# Power_SolenoidKill.net
KiCad netlist of a schematic drawn in Altium Designer
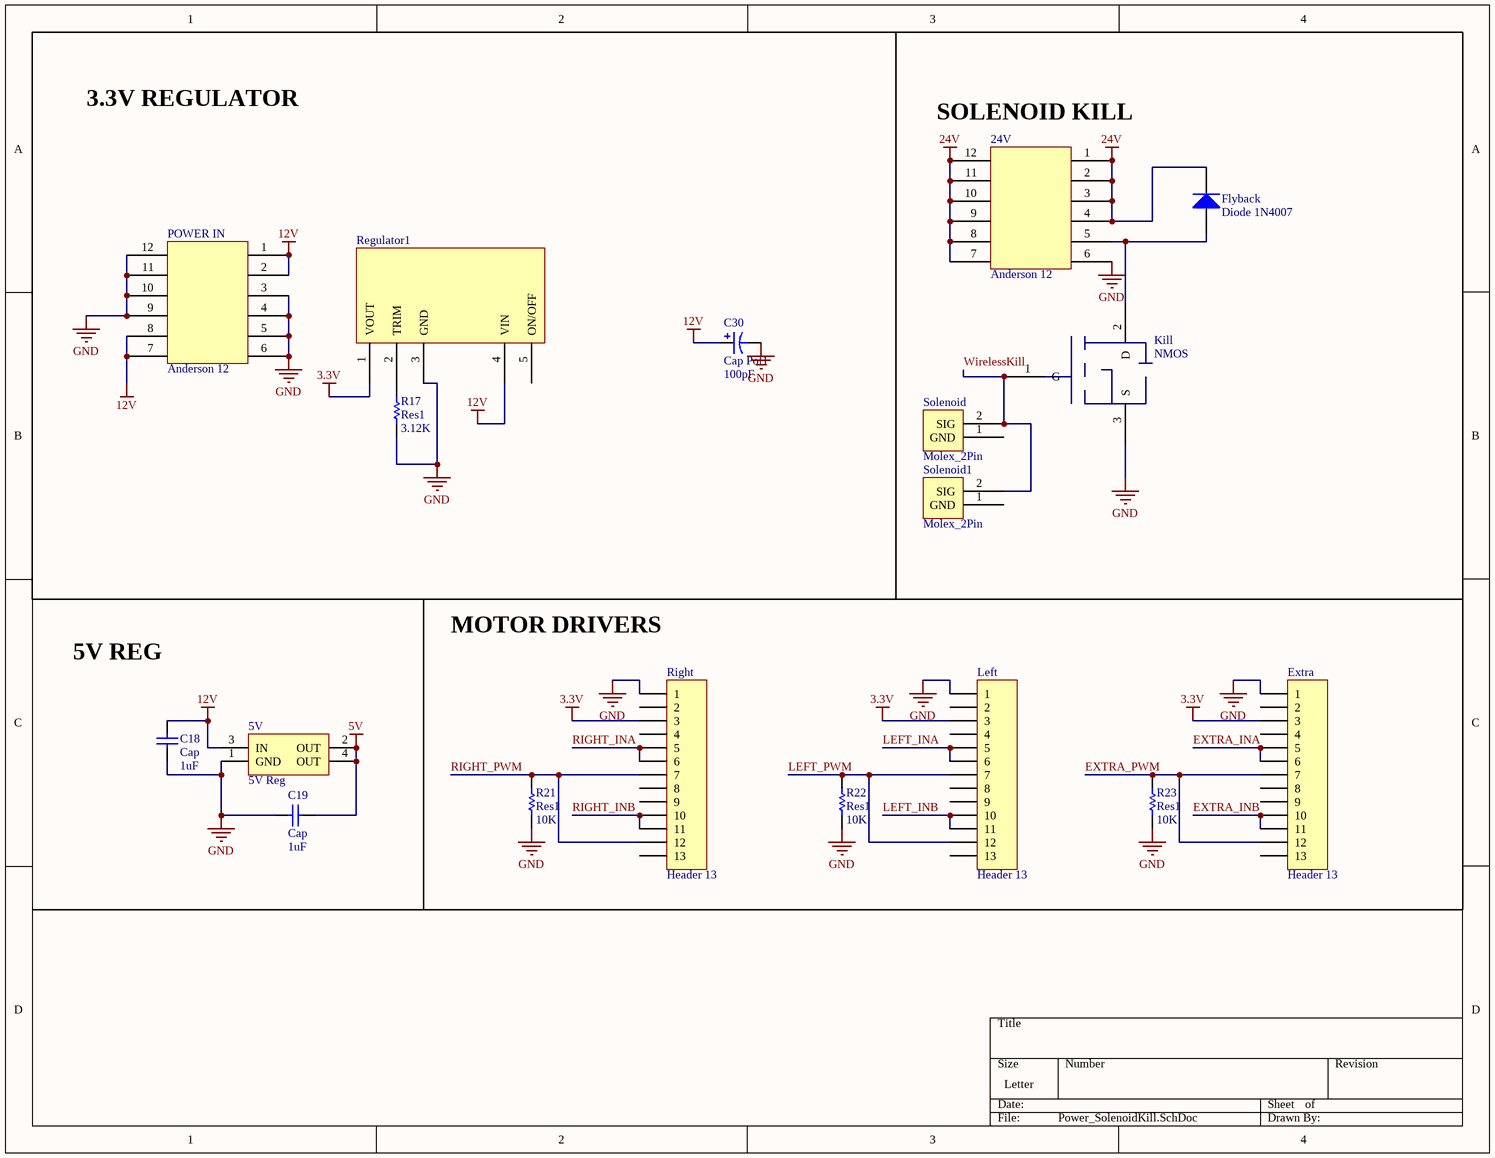
[diagram p0: Power_SolenoidKill.SchDoc]

(export (version "E")
  (design (tool "Eeschema 10.0.6"))
  (components
    (comp (ref "5V")
      (value "5V Reg")
      (footprint "5V REG")
      (description "5V Linear Reg, 1.5A (Digi-Key: ADP3339AKCZ-5-R7CT-ND)")
      (libsource (lib "MowerLib") (part "5V Reg"))
    )
    (comp (ref "24V")
      (value "Anderson 12")
      (footprint "PCBComponent_1 - duplicate2")
      (libsource (lib "VPOL5A_PowerRegulator") (part "Anderson 12"))
    )
    (comp (ref "C18")
      (value "Cap")
      (footprint "1608[0603]")
      (description "Capacitor")
      (fields (field (name "ALTIUM_VALUE") "1uF") (field (name "PUBLISHER") "Altium Limited"))
      (libsource (lib "Miscellaneous Devices") (part "Cap"))
    )
    (comp (ref "C19")
      (value "Cap")
      (footprint "1608[0603]")
      (description "Capacitor")
      (fields (field (name "ALTIUM_VALUE") "1uF") (field (name "PUBLISHER") "Altium Limited"))
      (libsource (lib "Miscellaneous Devices") (part "Cap"))
    )
    (comp (ref "C30")
      (value "Cap Pol1")
      (footprint "RB5-10.5")
      (description "Polarized Capacitor (Radial)")
      (fields (field (name "ALTIUM_VALUE") "100pF") (field (name "PUBLISHER") "Altium Limited"))
      (libsource (lib "Miscellaneous Devices") (part "Cap Pol1"))
    )
    (comp (ref "Extra")
      (value "Header 13")
      (footprint "HDR1X13")
      (description "Header, 13-Pin")
      (fields (field (name "PUBLISHER") "Altium Limited"))
      (libsource (lib "Miscellaneous Connectors") (part "Header 13"))
    )
    (comp (ref "Flyback")
      (value "Diode 1N4007")
      (footprint "DO-41")
      (description "1 Amp General Purpose Rectifier")
      (fields (field (name "PUBLISHER") "Altium Limited"))
      (libsource (lib "Miscellaneous Devices") (part "Diode 1N4007"))
    )
    (comp (ref "Kill") (value "NMOS") (footprint "TO229P990X239-3N") (libsource (lib "NMOS") (part "NMOS")))
    (comp (ref "Left")
      (value "Header 13")
      (footprint "HDR1X13")
      (description "Header, 13-Pin")
      (fields (field (name "PUBLISHER") "Altium Limited"))
      (libsource (lib "Miscellaneous Connectors") (part "Header 13"))
    )
    (comp (ref "POWER IN")
      (value "Anderson 12")
      (footprint "PCBComponent_1 - duplicate2")
      (libsource (lib "VPOL5A_PowerRegulator") (part "Anderson 12"))
    )
    (comp (ref "R17")
      (value "Res1")
      (footprint "1608[0603]")
      (description "Resistor")
      (fields (field (name "ALTIUM_VALUE") "3.12K") (field (name "PUBLISHER") "Altium Limited"))
      (libsource (lib "Miscellaneous Devices") (part "Res1"))
    )
    (comp (ref "R21")
      (value "Res1")
      (footprint "1608[0603]")
      (description "Resistor")
      (fields (field (name "ALTIUM_VALUE") "10K") (field (name "PUBLISHER") "Altium Limited"))
      (libsource (lib "Miscellaneous Devices") (part "Res1"))
    )
    (comp (ref "R22")
      (value "Res1")
      (footprint "1608[0603]")
      (description "Resistor")
      (fields (field (name "ALTIUM_VALUE") "10K") (field (name "PUBLISHER") "Altium Limited"))
      (libsource (lib "Miscellaneous Devices") (part "Res1"))
    )
    (comp (ref "R23")
      (value "Res1")
      (footprint "1608[0603]")
      (description "Resistor")
      (fields (field (name "ALTIUM_VALUE") "10K") (field (name "PUBLISHER") "Altium Limited"))
      (libsource (lib "Miscellaneous Devices") (part "Res1"))
    )
    (comp (ref "Regulator1")
      (value "Regulator")
      (footprint "PCBComponent_1")
      (libsource (lib "VPOL5A_PowerRegulator") (part "Regulator"))
    )
    (comp (ref "Right")
      (value "Header 13")
      (footprint "HDR1X13")
      (description "Header, 13-Pin")
      (fields (field (name "PUBLISHER") "Altium Limited"))
      (libsource (lib "Miscellaneous Connectors") (part "Header 13"))
    )
    (comp (ref "Solenoid")
      (value "Molex_2Pin")
      (footprint "PCBComponent_1")
      (libsource (lib "Molex_2Pin") (part "Molex_2Pin"))
    )
    (comp (ref "Solenoid1")
      (value "Molex_2Pin")
      (footprint "PCBComponent_1")
      (libsource (lib "Molex_2Pin") (part "Molex_2Pin"))
    )
  )
  (nets
    (net (code "1") (name "/EXTRA_INA") (class "Default")
      (node (ref "Extra") (pin "5") (pinfunction "5_5") (pintype "passive"))
      (node (ref "Extra") (pin "6") (pinfunction "6_6") (pintype "passive"))
    )
    (net (code "2") (name "/EXTRA_INB") (class "Default")
      (node (ref "Extra") (pin "10") (pinfunction "10_10") (pintype "passive"))
      (node (ref "Extra") (pin "11") (pinfunction "11_11") (pintype "passive"))
    )
    (net (code "3") (name "/EXTRA_PWM") (class "Default")
      (node (ref "Extra") (pin "12") (pinfunction "12_12") (pintype "passive"))
      (node (ref "Extra") (pin "7") (pinfunction "7_7") (pintype "passive"))
      (node (ref "R23") (pin "2") (pinfunction "2_2") (pintype "passive"))
    )
    (net (code "4") (name "/LEFT_INA") (class "Default")
      (node (ref "Left") (pin "5") (pinfunction "5_5") (pintype "passive"))
      (node (ref "Left") (pin "6") (pinfunction "6_6") (pintype "passive"))
    )
    (net (code "5") (name "/LEFT_INB") (class "Default")
      (node (ref "Left") (pin "10") (pinfunction "10_10") (pintype "passive"))
      (node (ref "Left") (pin "11") (pinfunction "11_11") (pintype "passive"))
    )
    (net (code "6") (name "/LEFT_PWM") (class "Default")
      (node (ref "Left") (pin "12") (pinfunction "12_12") (pintype "passive"))
      (node (ref "Left") (pin "7") (pinfunction "7_7") (pintype "passive"))
      (node (ref "R22") (pin "2") (pinfunction "2_2") (pintype "passive"))
    )
    (net (code "7") (name "/RIGHT_INA") (class "Default")
      (node (ref "Right") (pin "5") (pinfunction "5_5") (pintype "passive"))
      (node (ref "Right") (pin "6") (pinfunction "6_6") (pintype "passive"))
    )
    (net (code "8") (name "/RIGHT_INB") (class "Default")
      (node (ref "Right") (pin "10") (pinfunction "10_10") (pintype "passive"))
      (node (ref "Right") (pin "11") (pinfunction "11_11") (pintype "passive"))
    )
    (net (code "9") (name "/RIGHT_PWM") (class "Default")
      (node (ref "R21") (pin "2") (pinfunction "2_2") (pintype "passive"))
      (node (ref "Right") (pin "12") (pinfunction "12_12") (pintype "passive"))
      (node (ref "Right") (pin "7") (pinfunction "7_7") (pintype "passive"))
    )
    (net (code "10") (name "/WirelessKill") (class "Default")
      (node (ref "Kill") (pin "1") (pinfunction "G_1") (pintype "power_in"))
      (node (ref "Solenoid") (pin "2") (pinfunction "SIG_2") (pintype "passive"))
      (node (ref "Solenoid1") (pin "2") (pinfunction "SIG_2") (pintype "passive"))
    )
    (net (code "11") (name "3.3V") (class "Default")
      (node (ref "Extra") (pin "3") (pinfunction "3_3") (pintype "passive"))
      (node (ref "Left") (pin "3") (pinfunction "3_3") (pintype "passive"))
      (node (ref "Regulator1") (pin "1") (pinfunction "VOUT_1") (pintype "power_in"))
      (node (ref "Right") (pin "3") (pinfunction "3_3") (pintype "passive"))
    )
    (net (code "12") (name "5V") (class "Default")
      (node (ref "5V") (pin "2") (pinfunction "OUT_2") (pintype "power_in"))
      (node (ref "5V") (pin "4") (pinfunction "OUT_4") (pintype "power_in"))
      (node (ref "C19") (pin "1") (pinfunction "1_1") (pintype "passive"))
    )
    (net (code "13") (name "12V") (class "Default")
      (node (ref "5V") (pin "3") (pinfunction "IN_3") (pintype "power_in"))
      (node (ref "C18") (pin "1") (pinfunction "1_1") (pintype "passive"))
      (node (ref "C30") (pin "1") (pinfunction "1_1") (pintype "passive"))
      (node (ref "POWER IN") (pin "1") (pintype "passive"))
      (node (ref "POWER IN") (pin "2") (pintype "passive"))
      (node (ref "POWER IN") (pin "7") (pintype "passive"))
      (node (ref "POWER IN") (pin "8") (pintype "passive"))
      (node (ref "Regulator1") (pin "4") (pinfunction "VIN_4") (pintype "power_in"))
    )
    (net (code "14") (name "24V") (class "Default")
      (node (ref "24V") (pin "1") (pintype "passive"))
      (node (ref "24V") (pin "10") (pinfunction "10_10") (pintype "passive"))
      (node (ref "24V") (pin "11") (pinfunction "11_11") (pintype "passive"))
      (node (ref "24V") (pin "12") (pinfunction "12_12") (pintype "passive"))
      (node (ref "24V") (pin "2") (pintype "passive"))
      (node (ref "24V") (pin "3") (pintype "passive"))
      (node (ref "24V") (pin "4") (pintype "passive"))
      (node (ref "24V") (pin "7") (pintype "passive"))
      (node (ref "24V") (pin "8") (pintype "passive"))
      (node (ref "24V") (pin "9") (pinfunction "9_9") (pintype "passive"))
      (node (ref "Flyback") (pin "2") (pinfunction "K_2") (pintype "passive"))
    )
    (net (code "15") (name "GND") (class "Default")
      (node (ref "24V") (pin "6") (pintype "passive"))
      (node (ref "5V") (pin "1") (pinfunction "GND_1") (pintype "power_in"))
      (node (ref "C18") (pin "2") (pinfunction "2_2") (pintype "passive"))
      (node (ref "C19") (pin "2") (pinfunction "2_2") (pintype "passive"))
      (node (ref "C30") (pin "2") (pinfunction "2_2") (pintype "passive"))
      (node (ref "Extra") (pin "1") (pinfunction "1_1") (pintype "passive"))
      (node (ref "Kill") (pin "3") (pinfunction "S_3") (pintype "power_in"))
      (node (ref "Left") (pin "1") (pinfunction "1_1") (pintype "passive"))
      (node (ref "POWER IN") (pin "10") (pinfunction "10_10") (pintype "passive"))
      (node (ref "POWER IN") (pin "11") (pinfunction "11_11") (pintype "passive"))
      (node (ref "POWER IN") (pin "12") (pinfunction "12_12") (pintype "passive"))
      (node (ref "POWER IN") (pin "3") (pintype "passive"))
      (node (ref "POWER IN") (pin "4") (pintype "passive"))
      (node (ref "POWER IN") (pin "5") (pintype "passive"))
      (node (ref "POWER IN") (pin "6") (pintype "passive"))
      (node (ref "POWER IN") (pin "9") (pinfunction "9_9") (pintype "passive"))
      (node (ref "R17") (pin "1") (pinfunction "1_1") (pintype "passive"))
      (node (ref "R21") (pin "1") (pinfunction "1_1") (pintype "passive"))
      (node (ref "R22") (pin "1") (pinfunction "1_1") (pintype "passive"))
      (node (ref "R23") (pin "1") (pinfunction "1_1") (pintype "passive"))
      (node (ref "Regulator1") (pin "3") (pinfunction "GND_3") (pintype "power_in"))
      (node (ref "Right") (pin "1") (pinfunction "1_1") (pintype "passive"))
    )
    (net (code "16") (name "Net-(Flyback-A)") (class "Default")
      (node (ref "24V") (pin "5") (pintype "passive"))
      (node (ref "Flyback") (pin "1") (pinfunction "A_1") (pintype "passive"))
      (node (ref "Kill") (pin "2") (pinfunction "D_2") (pintype "power_in"))
    )
    (net (code "17") (name "Net-(Regulator1-TRIM)") (class "Default")
      (node (ref "R17") (pin "2") (pinfunction "2_2") (pintype "passive"))
      (node (ref "Regulator1") (pin "2") (pinfunction "TRIM_2") (pintype "passive"))
    )
    (net (code "18") (name "unconnected-(Extra-Pad2)") (class "Default")
      (node (ref "Extra") (pin "2") (pinfunction "2_2") (pintype "passive"))
    )
    (net (code "19") (name "unconnected-(Extra-Pad4)") (class "Default")
      (node (ref "Extra") (pin "4") (pinfunction "4_4") (pintype "passive"))
    )
    (net (code "20") (name "unconnected-(Extra-Pad8)") (class "Default")
      (node (ref "Extra") (pin "8") (pinfunction "8_8") (pintype "passive"))
    )
    (net (code "21") (name "unconnected-(Extra-Pad9)") (class "Default")
      (node (ref "Extra") (pin "9") (pinfunction "9_9") (pintype "passive"))
    )
    (net (code "22") (name "unconnected-(Extra-Pad13)") (class "Default")
      (node (ref "Extra") (pin "13") (pinfunction "13_13") (pintype "passive"))
    )
    (net (code "23") (name "unconnected-(Left-Pad2)") (class "Default")
      (node (ref "Left") (pin "2") (pinfunction "2_2") (pintype "passive"))
    )
    (net (code "24") (name "unconnected-(Left-Pad4)") (class "Default")
      (node (ref "Left") (pin "4") (pinfunction "4_4") (pintype "passive"))
    )
    (net (code "25") (name "unconnected-(Left-Pad8)") (class "Default")
      (node (ref "Left") (pin "8") (pinfunction "8_8") (pintype "passive"))
    )
    (net (code "26") (name "unconnected-(Left-Pad9)") (class "Default")
      (node (ref "Left") (pin "9") (pinfunction "9_9") (pintype "passive"))
    )
    (net (code "27") (name "unconnected-(Left-Pad13)") (class "Default")
      (node (ref "Left") (pin "13") (pinfunction "13_13") (pintype "passive"))
    )
    (net (code "28") (name "unconnected-(Regulator1-ON{slash}OFF-Pad5)") (class "Default")
      (node (ref "Regulator1") (pin "5") (pinfunction "ON/OFF_5") (pintype "passive"))
    )
    (net (code "29") (name "unconnected-(Right-Pad2)") (class "Default")
      (node (ref "Right") (pin "2") (pinfunction "2_2") (pintype "passive"))
    )
    (net (code "30") (name "unconnected-(Right-Pad4)") (class "Default")
      (node (ref "Right") (pin "4") (pinfunction "4_4") (pintype "passive"))
    )
    (net (code "31") (name "unconnected-(Right-Pad8)") (class "Default")
      (node (ref "Right") (pin "8") (pinfunction "8_8") (pintype "passive"))
    )
    (net (code "32") (name "unconnected-(Right-Pad9)") (class "Default")
      (node (ref "Right") (pin "9") (pinfunction "9_9") (pintype "passive"))
    )
    (net (code "33") (name "unconnected-(Right-Pad13)") (class "Default")
      (node (ref "Right") (pin "13") (pinfunction "13_13") (pintype "passive"))
    )
    (net (code "34") (name "unconnected-(Solenoid-GND-Pad1)") (class "Default")
      (node (ref "Solenoid") (pin "1") (pinfunction "GND_1") (pintype "power_in"))
    )
    (net (code "35") (name "unconnected-(Solenoid1-GND-Pad1)") (class "Default")
      (node (ref "Solenoid1") (pin "1") (pinfunction "GND_1") (pintype "power_in"))
    )
  )
)
